# 27CXXX.net
KiCad netlist of a schematic drawn in EAGLE
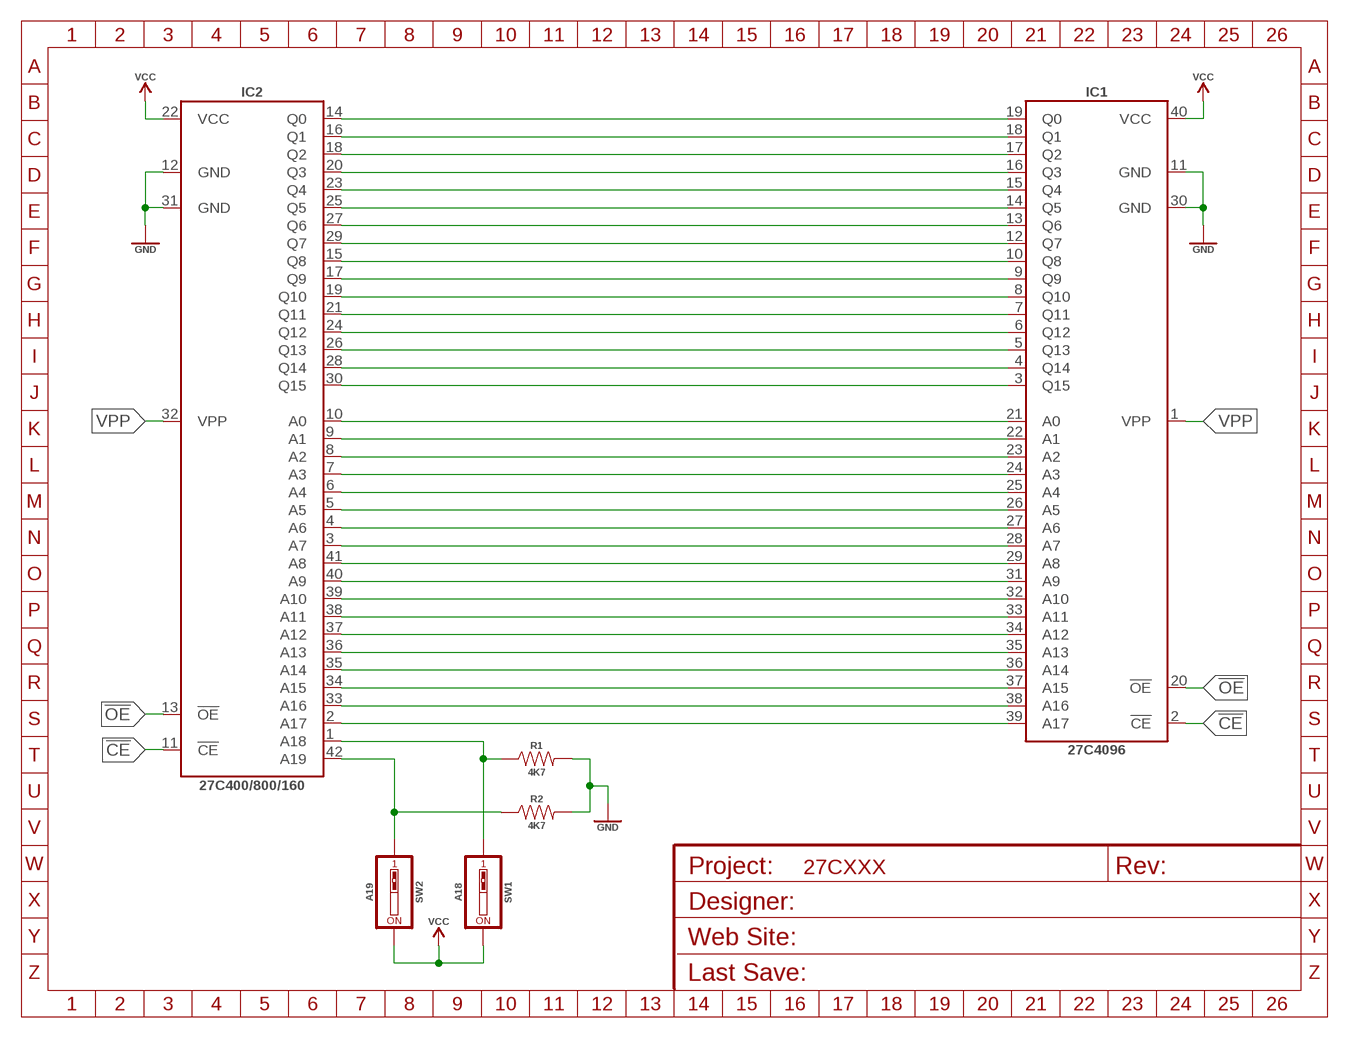
[diagram p0: schematic, sheet 1]

(export (version "E")
  (design (tool "Eeschema 10.0.6"))
  (components
    (comp (ref "IC1")
      (value "27C4096")
      (footprint "eagle-import:DIP40W")
      (libsource (lib "eagle-import") (part "27C4096_DIP"))
    )
    (comp (ref "IC2")
      (value "27C400/800/160")
      (footprint "eagle-import:ZIF42F")
      (libsource (lib "eagle-import") (part "27C160_ZIF42F"))
    )
    (comp (ref "R1")
      (value "4K7")
      (footprint "eagle-import:RESISTOR_0.3")
      (libsource (lib "eagle-import") (part "RESISTOR_THT_0.3"))
    )
    (comp (ref "R2")
      (value "4K7")
      (footprint "eagle-import:RESISTOR_0.3")
      (libsource (lib "eagle-import") (part "RESISTOR_THT_0.3"))
    )
    (comp (ref "SW1")
      (value "A18")
      (footprint "eagle-import:SWITCH_DIP_01")
      (libsource (lib "eagle-import") (part "SWITCH_DIP_01"))
    )
    (comp (ref "SW2")
      (value "A19")
      (footprint "eagle-import:SWITCH_DIP_01")
      (libsource (lib "eagle-import") (part "SWITCH_DIP_01"))
    )
  )
  (nets
    (net (code "1") (name "/~{CE}") (class "Default")
      (node (ref "IC1") (pin "2") (pinfunction "~{CE}_2") (pintype "bidirectional"))
      (node (ref "IC2") (pin "11") (pinfunction "~{CE}_11") (pintype "bidirectional"))
    )
    (net (code "2") (name "/~{OE}") (class "Default")
      (node (ref "IC1") (pin "20") (pinfunction "~{OE}_20") (pintype "bidirectional"))
      (node (ref "IC2") (pin "13") (pinfunction "~{OE}_13") (pintype "bidirectional"))
    )
    (net (code "3") (name "GND") (class "Default")
      (node (ref "IC1") (pin "11") (pinfunction "GND_11") (pintype "power_in"))
      (node (ref "IC1") (pin "30") (pinfunction "GND_30") (pintype "power_in"))
      (node (ref "IC2") (pin "12") (pinfunction "GND_12") (pintype "power_in"))
      (node (ref "IC2") (pin "31") (pinfunction "GND_31") (pintype "power_in"))
      (node (ref "R1") (pin "2") (pinfunction "2_2") (pintype "passive"))
      (node (ref "R2") (pin "2") (pinfunction "2_2") (pintype "passive"))
    )
    (net (code "4") (name "Net-(IC1-A0)") (class "Default")
      (node (ref "IC1") (pin "21") (pinfunction "A0_21") (pintype "bidirectional"))
      (node (ref "IC2") (pin "10") (pinfunction "A0_10") (pintype "bidirectional"))
    )
    (net (code "5") (name "Net-(IC1-A1)") (class "Default")
      (node (ref "IC1") (pin "22") (pinfunction "A1_22") (pintype "bidirectional"))
      (node (ref "IC2") (pin "9") (pinfunction "A1_9") (pintype "bidirectional"))
    )
    (net (code "6") (name "Net-(IC1-A2)") (class "Default")
      (node (ref "IC1") (pin "23") (pinfunction "A2_23") (pintype "bidirectional"))
      (node (ref "IC2") (pin "8") (pinfunction "A2_8") (pintype "bidirectional"))
    )
    (net (code "7") (name "Net-(IC1-A3)") (class "Default")
      (node (ref "IC1") (pin "24") (pinfunction "A3_24") (pintype "bidirectional"))
      (node (ref "IC2") (pin "7") (pinfunction "A3_7") (pintype "bidirectional"))
    )
    (net (code "8") (name "Net-(IC1-A4)") (class "Default")
      (node (ref "IC1") (pin "25") (pinfunction "A4_25") (pintype "bidirectional"))
      (node (ref "IC2") (pin "6") (pinfunction "A4_6") (pintype "bidirectional"))
    )
    (net (code "9") (name "Net-(IC1-A5)") (class "Default")
      (node (ref "IC1") (pin "26") (pinfunction "A5_26") (pintype "bidirectional"))
      (node (ref "IC2") (pin "5") (pinfunction "A5_5") (pintype "bidirectional"))
    )
    (net (code "10") (name "Net-(IC1-A6)") (class "Default")
      (node (ref "IC1") (pin "27") (pinfunction "A6_27") (pintype "bidirectional"))
      (node (ref "IC2") (pin "4") (pinfunction "A6_4") (pintype "bidirectional"))
    )
    (net (code "11") (name "Net-(IC1-A7)") (class "Default")
      (node (ref "IC1") (pin "28") (pinfunction "A7_28") (pintype "bidirectional"))
      (node (ref "IC2") (pin "3") (pinfunction "A7_3") (pintype "bidirectional"))
    )
    (net (code "12") (name "Net-(IC1-A8)") (class "Default")
      (node (ref "IC1") (pin "29") (pinfunction "A8_29") (pintype "bidirectional"))
      (node (ref "IC2") (pin "41") (pinfunction "A8_41") (pintype "bidirectional"))
    )
    (net (code "13") (name "Net-(IC1-A9)") (class "Default")
      (node (ref "IC1") (pin "31") (pinfunction "A9_31") (pintype "bidirectional"))
      (node (ref "IC2") (pin "40") (pinfunction "A9_40") (pintype "bidirectional"))
    )
    (net (code "14") (name "Net-(IC1-A10)") (class "Default")
      (node (ref "IC1") (pin "32") (pinfunction "A10_32") (pintype "bidirectional"))
      (node (ref "IC2") (pin "39") (pinfunction "A10_39") (pintype "bidirectional"))
    )
    (net (code "15") (name "Net-(IC1-A11)") (class "Default")
      (node (ref "IC1") (pin "33") (pinfunction "A11_33") (pintype "bidirectional"))
      (node (ref "IC2") (pin "38") (pinfunction "A11_38") (pintype "bidirectional"))
    )
    (net (code "16") (name "Net-(IC1-A12)") (class "Default")
      (node (ref "IC1") (pin "34") (pinfunction "A12_34") (pintype "bidirectional"))
      (node (ref "IC2") (pin "37") (pinfunction "A12_37") (pintype "bidirectional"))
    )
    (net (code "17") (name "Net-(IC1-A13)") (class "Default")
      (node (ref "IC1") (pin "35") (pinfunction "A13_35") (pintype "bidirectional"))
      (node (ref "IC2") (pin "36") (pinfunction "A13_36") (pintype "bidirectional"))
    )
    (net (code "18") (name "Net-(IC1-A14)") (class "Default")
      (node (ref "IC1") (pin "36") (pinfunction "A14_36") (pintype "bidirectional"))
      (node (ref "IC2") (pin "35") (pinfunction "A14_35") (pintype "bidirectional"))
    )
    (net (code "19") (name "Net-(IC1-A15)") (class "Default")
      (node (ref "IC1") (pin "37") (pinfunction "A15_37") (pintype "bidirectional"))
      (node (ref "IC2") (pin "34") (pinfunction "A15_34") (pintype "bidirectional"))
    )
    (net (code "20") (name "Net-(IC1-A16)") (class "Default")
      (node (ref "IC1") (pin "38") (pinfunction "A16_38") (pintype "bidirectional"))
      (node (ref "IC2") (pin "33") (pinfunction "A16_33") (pintype "bidirectional"))
    )
    (net (code "21") (name "Net-(IC1-A17)") (class "Default")
      (node (ref "IC1") (pin "39") (pinfunction "A17_39") (pintype "bidirectional"))
      (node (ref "IC2") (pin "2") (pinfunction "A17_2") (pintype "bidirectional"))
    )
    (net (code "22") (name "Net-(IC1-Q0)") (class "Default")
      (node (ref "IC1") (pin "19") (pinfunction "Q0_19") (pintype "bidirectional"))
      (node (ref "IC2") (pin "14") (pinfunction "Q0_14") (pintype "bidirectional"))
    )
    (net (code "23") (name "Net-(IC1-Q1)") (class "Default")
      (node (ref "IC1") (pin "18") (pinfunction "Q1_18") (pintype "bidirectional"))
      (node (ref "IC2") (pin "16") (pinfunction "Q1_16") (pintype "bidirectional"))
    )
    (net (code "24") (name "Net-(IC1-Q2)") (class "Default")
      (node (ref "IC1") (pin "17") (pinfunction "Q2_17") (pintype "bidirectional"))
      (node (ref "IC2") (pin "18") (pinfunction "Q2_18") (pintype "bidirectional"))
    )
    (net (code "25") (name "Net-(IC1-Q3)") (class "Default")
      (node (ref "IC1") (pin "16") (pinfunction "Q3_16") (pintype "bidirectional"))
      (node (ref "IC2") (pin "20") (pinfunction "Q3_20") (pintype "bidirectional"))
    )
    (net (code "26") (name "Net-(IC1-Q4)") (class "Default")
      (node (ref "IC1") (pin "15") (pinfunction "Q4_15") (pintype "bidirectional"))
      (node (ref "IC2") (pin "23") (pinfunction "Q4_23") (pintype "bidirectional"))
    )
    (net (code "27") (name "Net-(IC1-Q5)") (class "Default")
      (node (ref "IC1") (pin "14") (pinfunction "Q5_14") (pintype "bidirectional"))
      (node (ref "IC2") (pin "25") (pinfunction "Q5_25") (pintype "bidirectional"))
    )
    (net (code "28") (name "Net-(IC1-Q6)") (class "Default")
      (node (ref "IC1") (pin "13") (pinfunction "Q6_13") (pintype "bidirectional"))
      (node (ref "IC2") (pin "27") (pinfunction "Q6_27") (pintype "bidirectional"))
    )
    (net (code "29") (name "Net-(IC1-Q7)") (class "Default")
      (node (ref "IC1") (pin "12") (pinfunction "Q7_12") (pintype "bidirectional"))
      (node (ref "IC2") (pin "29") (pinfunction "Q7_29") (pintype "bidirectional"))
    )
    (net (code "30") (name "Net-(IC1-Q8)") (class "Default")
      (node (ref "IC1") (pin "10") (pinfunction "Q8_10") (pintype "bidirectional"))
      (node (ref "IC2") (pin "15") (pinfunction "Q8_15") (pintype "bidirectional"))
    )
    (net (code "31") (name "Net-(IC1-Q9)") (class "Default")
      (node (ref "IC1") (pin "9") (pinfunction "Q9_9") (pintype "bidirectional"))
      (node (ref "IC2") (pin "17") (pinfunction "Q9_17") (pintype "bidirectional"))
    )
    (net (code "32") (name "Net-(IC1-Q10)") (class "Default")
      (node (ref "IC1") (pin "8") (pinfunction "Q10_8") (pintype "bidirectional"))
      (node (ref "IC2") (pin "19") (pinfunction "Q10_19") (pintype "bidirectional"))
    )
    (net (code "33") (name "Net-(IC1-Q11)") (class "Default")
      (node (ref "IC1") (pin "7") (pinfunction "Q11_7") (pintype "bidirectional"))
      (node (ref "IC2") (pin "21") (pinfunction "Q11_21") (pintype "bidirectional"))
    )
    (net (code "34") (name "Net-(IC1-Q12)") (class "Default")
      (node (ref "IC1") (pin "6") (pinfunction "Q12_6") (pintype "bidirectional"))
      (node (ref "IC2") (pin "24") (pinfunction "Q12_24") (pintype "bidirectional"))
    )
    (net (code "35") (name "Net-(IC1-Q13)") (class "Default")
      (node (ref "IC1") (pin "5") (pinfunction "Q13_5") (pintype "bidirectional"))
      (node (ref "IC2") (pin "26") (pinfunction "Q13_26") (pintype "bidirectional"))
    )
    (net (code "36") (name "Net-(IC1-Q14)") (class "Default")
      (node (ref "IC1") (pin "4") (pinfunction "Q14_4") (pintype "bidirectional"))
      (node (ref "IC2") (pin "28") (pinfunction "Q14_28") (pintype "bidirectional"))
    )
    (net (code "37") (name "Net-(IC1-Q15)") (class "Default")
      (node (ref "IC1") (pin "3") (pinfunction "Q15_3") (pintype "bidirectional"))
      (node (ref "IC2") (pin "30") (pinfunction "Q15_30") (pintype "bidirectional"))
    )
    (net (code "38") (name "Net-(IC2-A18)") (class "Default")
      (node (ref "IC2") (pin "1") (pinfunction "A18_1") (pintype "bidirectional"))
      (node (ref "R1") (pin "1") (pinfunction "1_1") (pintype "passive"))
      (node (ref "SW1") (pin "1") (pinfunction "1_1") (pintype "passive"))
    )
    (net (code "39") (name "Net-(IC2-A19)") (class "Default")
      (node (ref "IC2") (pin "42") (pinfunction "A19_42") (pintype "bidirectional"))
      (node (ref "R2") (pin "1") (pinfunction "1_1") (pintype "passive"))
      (node (ref "SW2") (pin "1") (pinfunction "1_1") (pintype "passive"))
    )
    (net (code "40") (name "VCC") (class "Default")
      (node (ref "IC1") (pin "40") (pinfunction "VCC_40") (pintype "power_in"))
      (node (ref "IC2") (pin "22") (pinfunction "VCC_22") (pintype "power_in"))
      (node (ref "SW1") (pin "2") (pinfunction "2_2") (pintype "passive"))
      (node (ref "SW2") (pin "2") (pinfunction "2_2") (pintype "passive"))
    )
    (net (code "41") (name "VPP") (class "Default")
      (node (ref "IC1") (pin "1") (pinfunction "VPP_1") (pintype "power_in"))
      (node (ref "IC2") (pin "32") (pinfunction "VPP_32") (pintype "power_in"))
    )
  )
)
